# RFID_System_Board.net
KiCad netlist of a schematic drawn in EAGLE
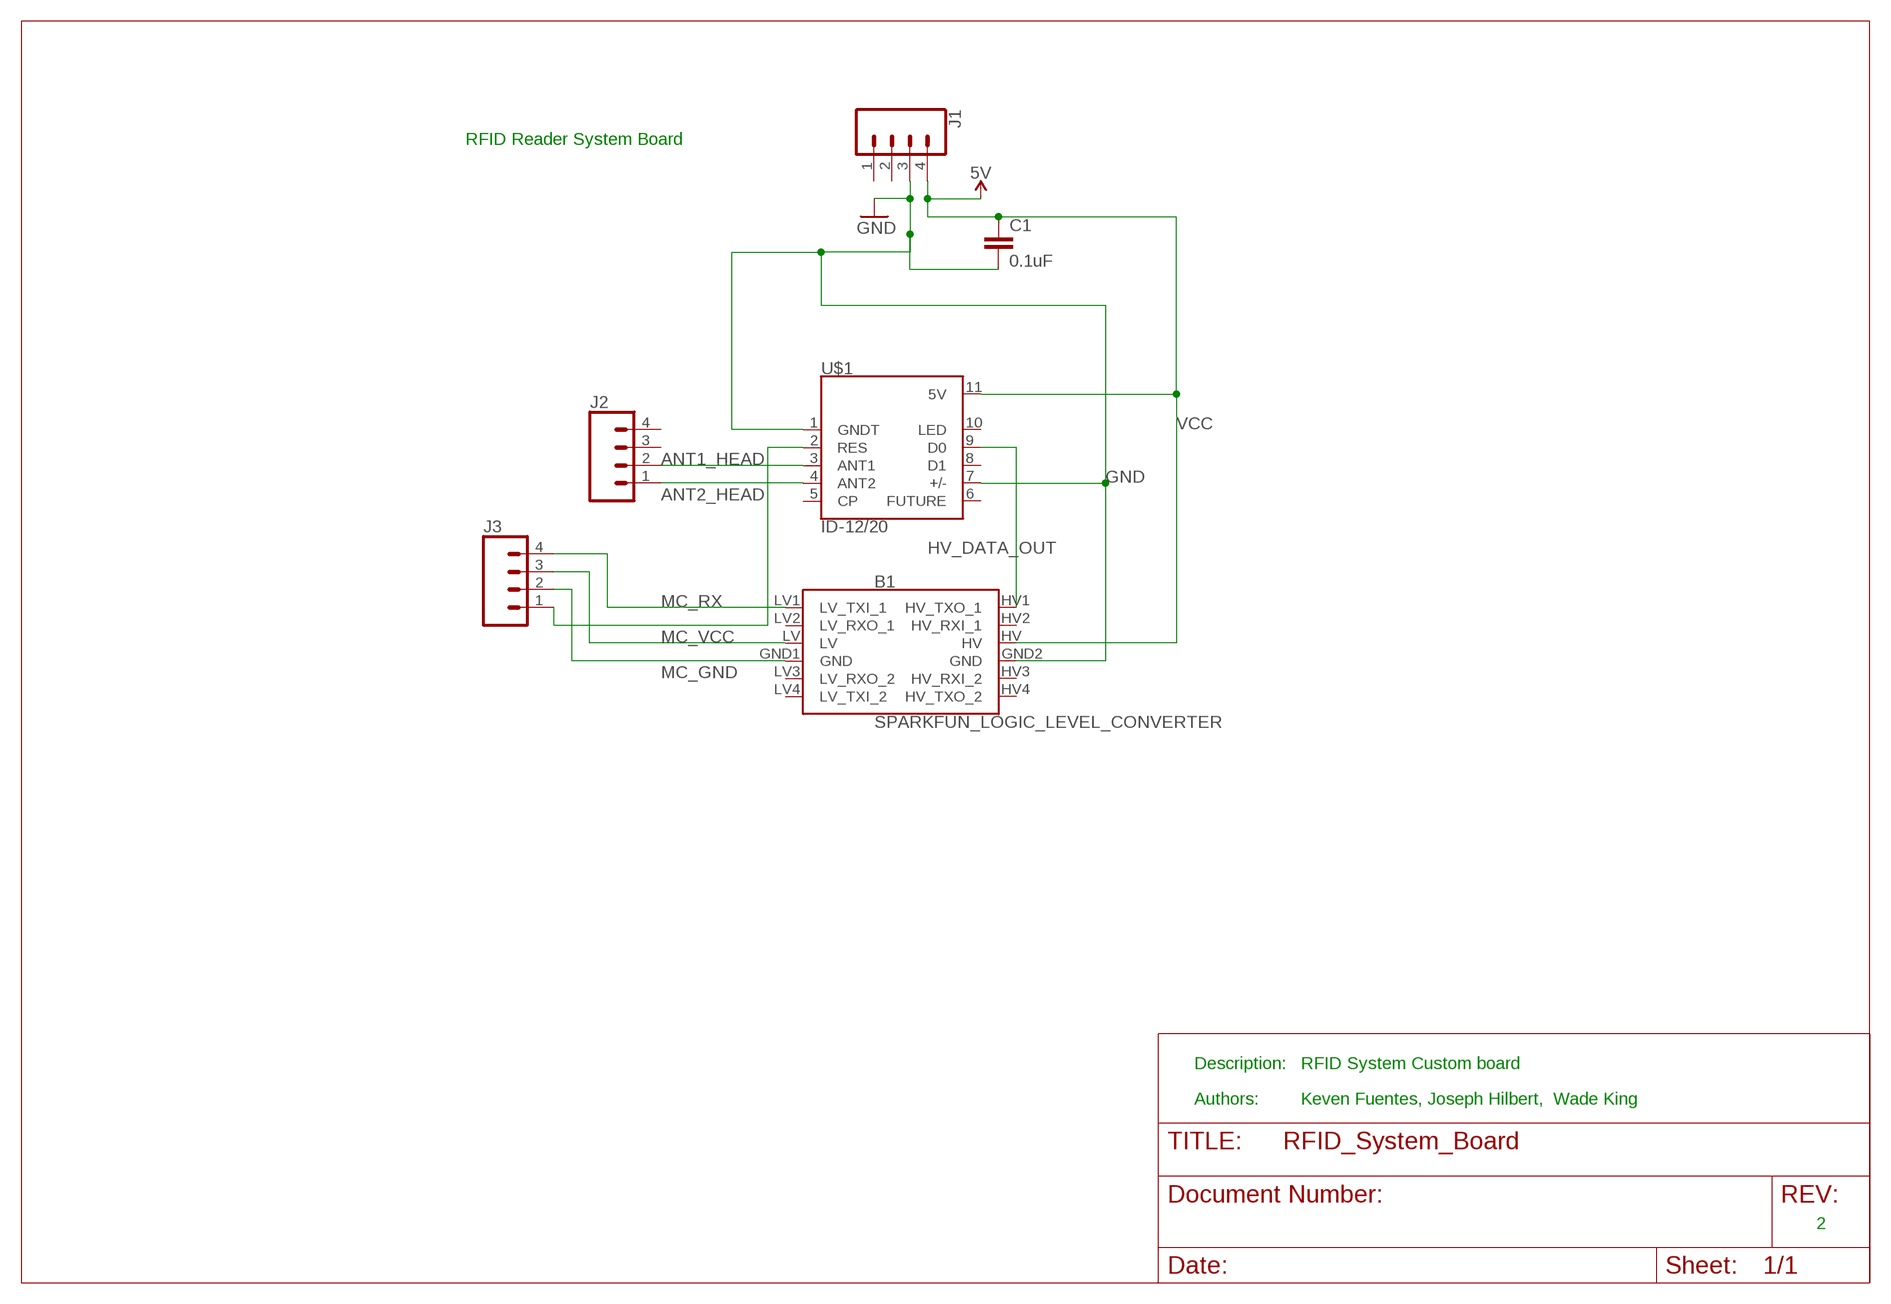
[diagram p0: schematic, sheet 1]

(export (version "E")
  (design (tool "Eeschema 10.0.6"))
  (components
    (comp (ref "B1")
      (value "SPARKFUN_LOGIC_LEVEL_CONVERTER")
      (footprint "eagle-import:SPARKFUN_LOGIC_LEVEL_CONVERTER")
      (libsource (lib "eagle-import") (part "SPARKFUN_LOGIC_LEVEL_CONVERTER"))
    )
    (comp (ref "C1")
      (value "0.1uF")
      (footprint "eagle-import:0603")
      (libsource (lib "eagle-import") (part "0.1UF-0603-25V-(+80/-20%)"))
    )
    (comp (ref "J1")
      (value "CONN_04")
      (footprint "eagle-import:1X04")
      (libsource (lib "eagle-import") (part "CONN_04"))
    )
    (comp (ref "J2")
      (value "CONN_04")
      (footprint "eagle-import:1X04")
      (libsource (lib "eagle-import") (part "CONN_04"))
    )
    (comp (ref "J3")
      (value "CONN_04")
      (footprint "eagle-import:1X04")
      (libsource (lib "eagle-import") (part "CONN_04"))
    )
    (comp (ref "U$1")
      (value "ID-12/20")
      (footprint "eagle-import:ID-12")
      (libsource (lib "eagle-import") (part "ID-12/20"))
    )
  )
  (nets
    (net (code "1") (name "/ANT1_HEAD") (class "Default")
      (node (ref "J2") (pin "2") (pinfunction "2_2") (pintype "passive"))
      (node (ref "U$1") (pin "3") (pinfunction "ANT1_3") (pintype "bidirectional"))
    )
    (net (code "2") (name "/ANT2_HEAD") (class "Default")
      (node (ref "J2") (pin "1") (pinfunction "1_1") (pintype "passive"))
      (node (ref "U$1") (pin "4") (pinfunction "ANT2_4") (pintype "bidirectional"))
    )
    (net (code "3") (name "/HV_DATA_OUT") (class "Default")
      (node (ref "B1") (pin "HV1") (pinfunction "HV_TXO_1_HV1") (pintype "bidirectional"))
      (node (ref "U$1") (pin "9") (pinfunction "D0_9") (pintype "bidirectional"))
    )
    (net (code "4") (name "/MC_GND") (class "Default")
      (node (ref "B1") (pin "GND1") (pinfunction "GND_GND1") (pintype "power_in"))
      (node (ref "J3") (pin "2") (pinfunction "2_2") (pintype "passive"))
    )
    (net (code "5") (name "/MC_RX") (class "Default")
      (node (ref "B1") (pin "LV1") (pinfunction "LV_TXI_1_LV1") (pintype "bidirectional"))
      (node (ref "J3") (pin "4") (pinfunction "4_4") (pintype "passive"))
    )
    (net (code "6") (name "/MC_VCC") (class "Default")
      (node (ref "B1") (pin "LV") (pinfunction "LV_LV") (pintype "power_in"))
      (node (ref "J3") (pin "3") (pinfunction "3_3") (pintype "passive"))
    )
    (net (code "7") (name "5V") (class "Default")
      (node (ref "B1") (pin "HV") (pinfunction "HV_HV") (pintype "power_in"))
      (node (ref "C1") (pin "1") (pinfunction "1_1") (pintype "passive"))
      (node (ref "J1") (pin "4") (pinfunction "4_4") (pintype "passive"))
      (node (ref "U$1") (pin "11") (pinfunction "5V_11") (pintype "bidirectional"))
    )
    (net (code "8") (name "GND") (class "Default")
      (node (ref "B1") (pin "GND2") (pinfunction "GND_GND2") (pintype "power_in"))
      (node (ref "C1") (pin "2") (pinfunction "2_2") (pintype "passive"))
      (node (ref "J1") (pin "3") (pinfunction "3_3") (pintype "passive"))
      (node (ref "U$1") (pin "1") (pinfunction "GNDT_1") (pintype "bidirectional"))
      (node (ref "U$1") (pin "7") (pinfunction "+/-_7") (pintype "bidirectional"))
    )
    (net (code "9") (name "Net-(U$1-RES)") (class "Default")
      (node (ref "J3") (pin "1") (pinfunction "1_1") (pintype "passive"))
      (node (ref "U$1") (pin "2") (pinfunction "RES_2") (pintype "bidirectional"))
    )
    (net (code "10") (name "unconnected-(B1-HV_RXI_1-PadHV2)") (class "Default")
      (node (ref "B1") (pin "HV2") (pinfunction "HV_RXI_1_HV2") (pintype "bidirectional"))
    )
    (net (code "11") (name "unconnected-(B1-HV_RXI_2-PadHV3)") (class "Default")
      (node (ref "B1") (pin "HV3") (pinfunction "HV_RXI_2_HV3") (pintype "bidirectional"))
    )
    (net (code "12") (name "unconnected-(B1-HV_TXO_2-PadHV4)") (class "Default")
      (node (ref "B1") (pin "HV4") (pinfunction "HV_TXO_2_HV4") (pintype "bidirectional"))
    )
    (net (code "13") (name "unconnected-(B1-LV_RXO_1-PadLV2)") (class "Default")
      (node (ref "B1") (pin "LV2") (pinfunction "LV_RXO_1_LV2") (pintype "bidirectional"))
    )
    (net (code "14") (name "unconnected-(B1-LV_RXO_2-PadLV3)") (class "Default")
      (node (ref "B1") (pin "LV3") (pinfunction "LV_RXO_2_LV3") (pintype "bidirectional"))
    )
    (net (code "15") (name "unconnected-(B1-LV_TXI_2-PadLV4)") (class "Default")
      (node (ref "B1") (pin "LV4") (pinfunction "LV_TXI_2_LV4") (pintype "bidirectional"))
    )
    (net (code "16") (name "unconnected-(J1-Pad1)") (class "Default")
      (node (ref "J1") (pin "1") (pinfunction "1_1") (pintype "passive"))
    )
    (net (code "17") (name "unconnected-(J1-Pad2)") (class "Default")
      (node (ref "J1") (pin "2") (pinfunction "2_2") (pintype "passive"))
    )
    (net (code "18") (name "unconnected-(J2-Pad3)") (class "Default")
      (node (ref "J2") (pin "3") (pinfunction "3_3") (pintype "passive"))
    )
    (net (code "19") (name "unconnected-(J2-Pad4)") (class "Default")
      (node (ref "J2") (pin "4") (pinfunction "4_4") (pintype "passive"))
    )
    (net (code "20") (name "unconnected-(U$1-CP-Pad5)") (class "Default")
      (node (ref "U$1") (pin "5") (pinfunction "CP_5") (pintype "bidirectional"))
    )
    (net (code "21") (name "unconnected-(U$1-D1-Pad8)") (class "Default")
      (node (ref "U$1") (pin "8") (pinfunction "D1_8") (pintype "bidirectional"))
    )
    (net (code "22") (name "unconnected-(U$1-FUTURE-Pad6)") (class "Default")
      (node (ref "U$1") (pin "6") (pinfunction "FUTURE_6") (pintype "bidirectional"))
    )
    (net (code "23") (name "unconnected-(U$1-LED-Pad10)") (class "Default")
      (node (ref "U$1") (pin "10") (pinfunction "LED_10") (pintype "bidirectional"))
    )
  )
)
